# DMotor_Schematic_page1.net
KiCad netlist of a schematic drawn in Altium Designer
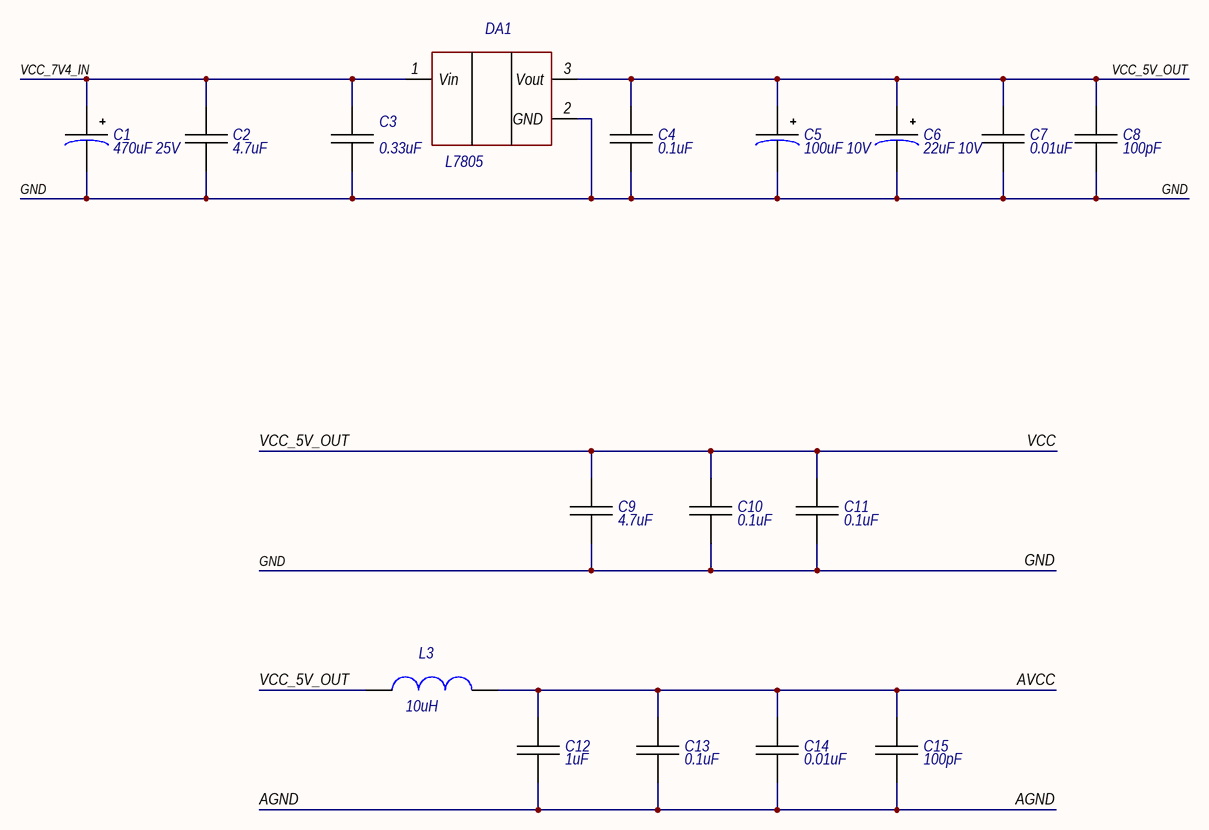
[diagram p0: DMotor_Schematic_page1.SchDoc]

(export (version "E")
  (design (tool "Eeschema 10.0.6"))
  (components
    (comp (ref "C1")
      (value "470uF 25V")
      (footprint "CapElec_8x16_3.5mm")
      (fields (field (name "MANUFACTURER") "JB"))
      (libsource (lib "Board_lib") (part "Capacitor_Elec"))
    )
    (comp (ref "C2")
      (value "4.7uF")
      (footprint "C0603")
      (fields (field (name "MANUFACTURER") "Murata"))
      (libsource (lib "Board_lib") (part "Capasitor"))
    )
    (comp (ref "C3")
      (value "0.33uF")
      (footprint "C0603")
      (fields (field (name "MANUFACTURER") "RUF"))
      (libsource (lib "Board_lib") (part "Capasitor"))
    )
    (comp (ref "C4")
      (value "0.1uF")
      (footprint "C0603")
      (description "X7R 50В 10% 0603")
      (fields (field (name "MANUFACTURER") "Murata"))
      (libsource (lib "Board_lib") (part "Capasitor"))
    )
    (comp (ref "C5")
      (value "100uF 10V")
      (footprint "CapElec_5x11_2mm")
      (fields (field (name "MANUFACTURER") "JB"))
      (libsource (lib "Board_lib") (part "Capacitor_Elec"))
    )
    (comp (ref "C6")
      (value "22uF 10V")
      (footprint "TANT-B")
      (libsource (lib "Board_lib") (part "Capasitor_Tantalum"))
    )
    (comp (ref "C7")
      (value "0.01uF")
      (footprint "C0603")
      (fields (field (name "MANUFACTURER") "Murata"))
      (libsource (lib "Board_lib") (part "Capasitor"))
    )
    (comp (ref "C8")
      (value "100pF")
      (footprint "C0603")
      (fields (field (name "MANUFACTURER") "Murata"))
      (libsource (lib "Board_lib") (part "Capasitor"))
    )
    (comp (ref "C9")
      (value "4.7uF")
      (footprint "C0603")
      (fields (field (name "MANUFACTURER") "Murata"))
      (libsource (lib "Board_lib") (part "Capasitor"))
    )
    (comp (ref "C10")
      (value "0.1uF")
      (footprint "C0603")
      (fields (field (name "MANUFACTURER") "Murata"))
      (libsource (lib "Board_lib") (part "Capasitor"))
    )
    (comp (ref "C11")
      (value "0.1uF")
      (footprint "C0603")
      (fields (field (name "MANUFACTURER") "Murata"))
      (libsource (lib "Board_lib") (part "Capasitor"))
    )
    (comp (ref "C12")
      (value "1uF")
      (footprint "C0603")
      (description "X7R 1мкФ 16В 10% 0603")
      (fields (field (name "MANUFACTURER") "Murata"))
      (libsource (lib "Board_lib") (part "Capasitor"))
    )
    (comp (ref "C13")
      (value "0.1uF")
      (footprint "C0603")
      (fields (field (name "MANUFACTURER") "Murata"))
      (libsource (lib "Board_lib") (part "Capasitor"))
    )
    (comp (ref "C14") (value "0.01uF") (footprint "C0603") (libsource (lib "Board_lib") (part "Capasitor")))
    (comp (ref "C15") (value "100pF") (footprint "C0603") (libsource (lib "Board_lib") (part "Capasitor")))
    (comp (ref "DA1")
      (value "L7805")
      (footprint "TO-220A")
      (description "Linear Voltage Regulator IC  1 Output  1.5A TO-220AB")
      (fields (field (name "MANUFACTURER") "STMicroelectronics"))
      (libsource (lib "Board_lib") (part "L75xx"))
    )
    (comp (ref "L3")
      (value "10uH")
      (footprint "IND1206")
      (fields (field (name "MANUFACTURER") "Murata"))
      (libsource (lib "Board_lib") (part "Inductivity"))
    )
  )
  (nets
    (net (code "1") (name "/AGND") (class "Default")
      (node (ref "C12") (pin "2") (pintype "passive"))
      (node (ref "C13") (pin "2") (pintype "passive"))
      (node (ref "C14") (pin "2") (pintype "passive"))
      (node (ref "C15") (pin "2") (pintype "passive"))
    )
    (net (code "2") (name "/AVCC") (class "Default")
      (node (ref "C12") (pin "1") (pintype "passive"))
      (node (ref "C13") (pin "1") (pintype "passive"))
      (node (ref "C14") (pin "1") (pintype "passive"))
      (node (ref "C15") (pin "1") (pintype "passive"))
      (node (ref "L3") (pin "2") (pintype "passive"))
    )
    (net (code "3") (name "/GND") (class "Default")
      (node (ref "C1") (pin "2") (pintype "passive"))
      (node (ref "C10") (pin "2") (pintype "passive"))
      (node (ref "C11") (pin "2") (pintype "passive"))
      (node (ref "C2") (pin "2") (pintype "passive"))
      (node (ref "C3") (pin "2") (pintype "passive"))
      (node (ref "C4") (pin "2") (pintype "passive"))
      (node (ref "C5") (pin "2") (pintype "passive"))
      (node (ref "C6") (pin "2") (pintype "passive"))
      (node (ref "C7") (pin "2") (pintype "passive"))
      (node (ref "C8") (pin "2") (pintype "passive"))
      (node (ref "C9") (pin "2") (pintype "passive"))
      (node (ref "DA1") (pin "2") (pinfunction "GND_2") (pintype "passive"))
    )
    (net (code "4") (name "/VCC") (class "Default")
      (node (ref "C10") (pin "1") (pintype "passive"))
      (node (ref "C11") (pin "1") (pintype "passive"))
      (node (ref "C4") (pin "1") (pintype "passive"))
      (node (ref "C5") (pin "1") (pintype "passive"))
      (node (ref "C6") (pin "1") (pintype "passive"))
      (node (ref "C7") (pin "1") (pintype "passive"))
      (node (ref "C8") (pin "1") (pintype "passive"))
      (node (ref "C9") (pin "1") (pintype "passive"))
      (node (ref "DA1") (pin "3") (pinfunction "Vout_3") (pintype "passive"))
      (node (ref "L3") (pin "1") (pintype "passive"))
    )
    (net (code "5") (name "/VCC_7V4_IN") (class "Default")
      (node (ref "C1") (pin "1") (pintype "passive"))
      (node (ref "C2") (pin "1") (pintype "passive"))
      (node (ref "C3") (pin "1") (pintype "passive"))
      (node (ref "DA1") (pin "1") (pinfunction "Vin_1") (pintype "passive"))
    )
  )
)
